# Solenoid_6.net
KiCad netlist of a schematic drawn in EAGLE
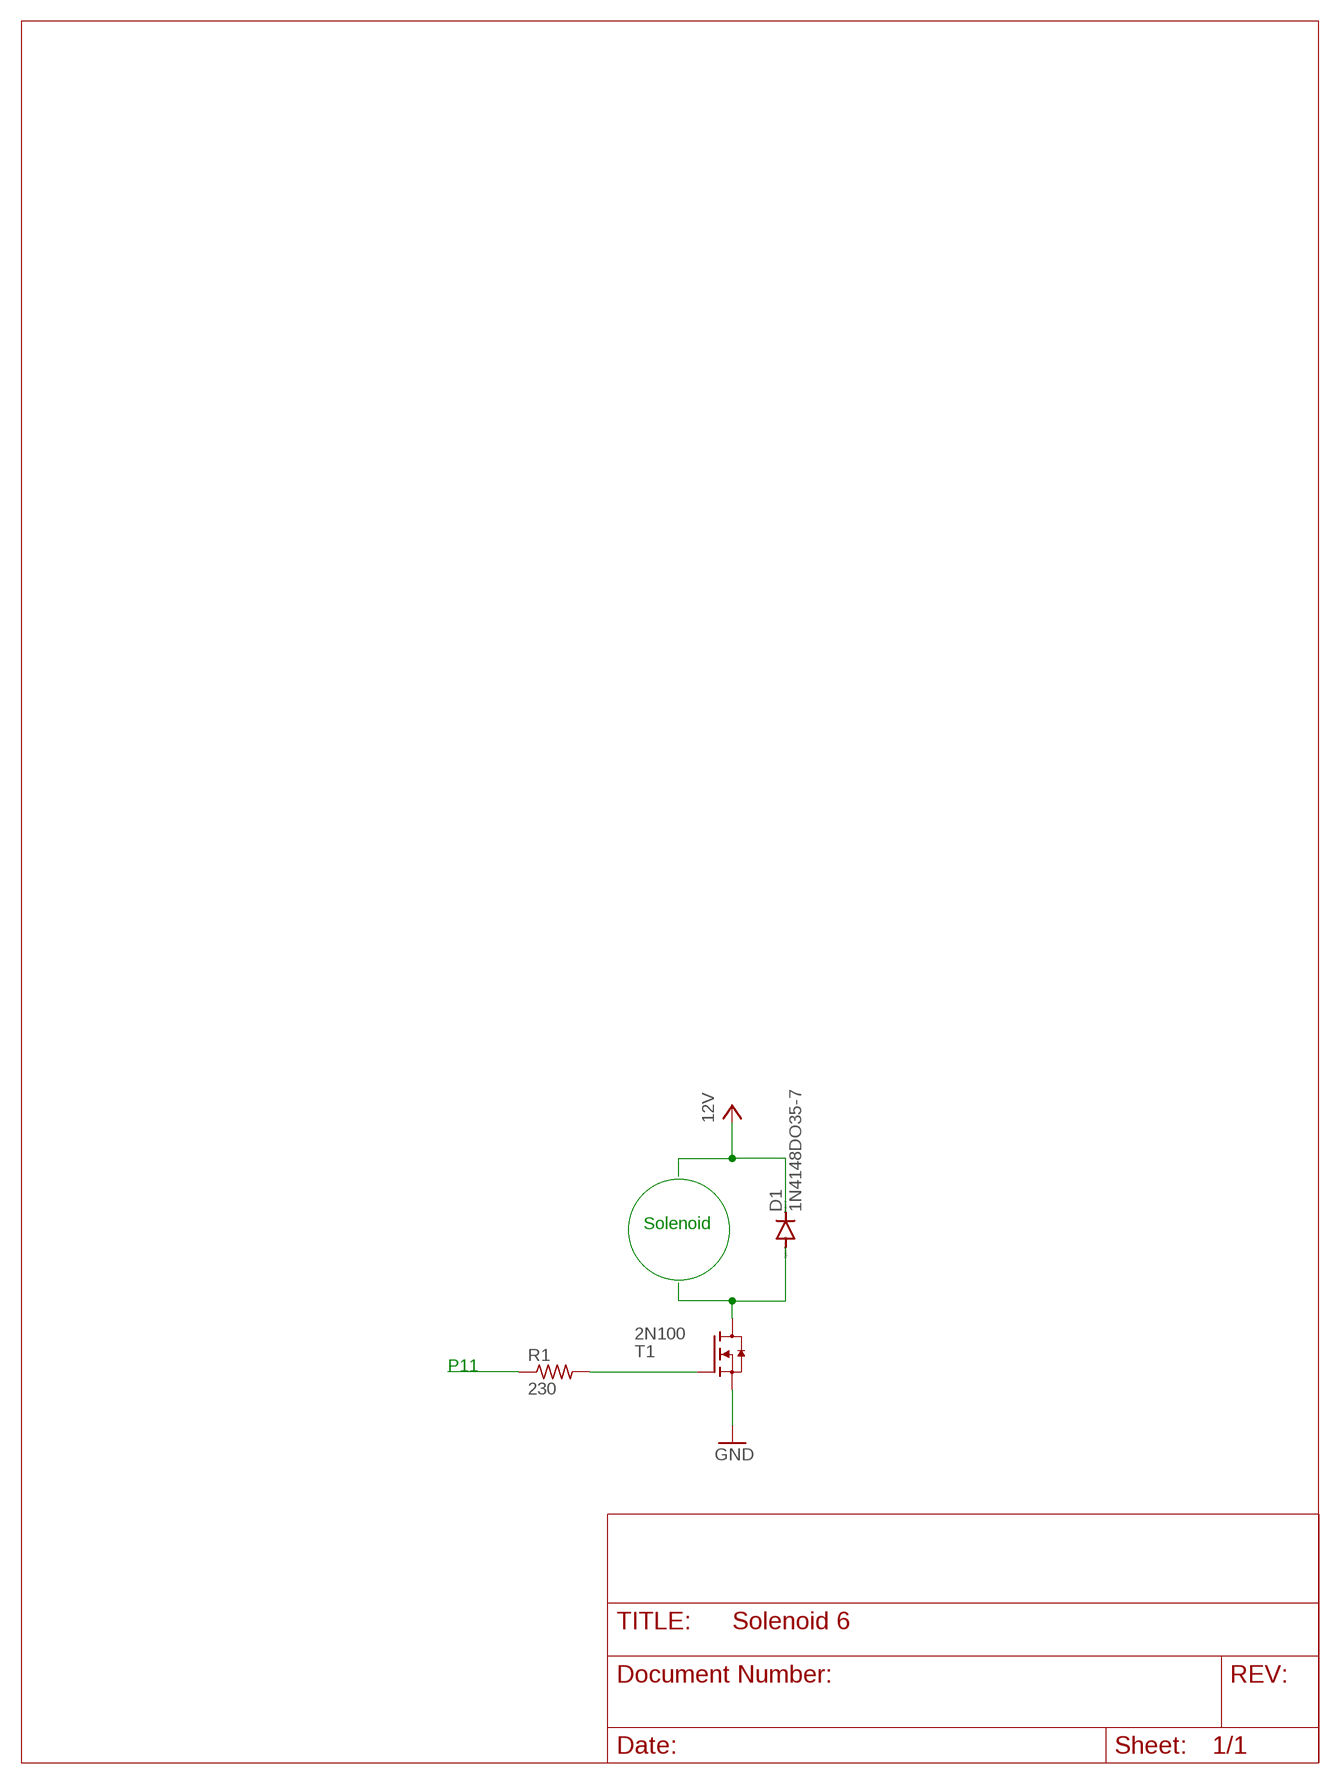
[diagram p0: schematic, sheet 1]

(export (version "E")
  (design (tool "Eeschema 10.0.6"))
  (components
    (comp (ref "D1")
      (value "1N4148DO35-7")
      (footprint "eagle-import:DO35-7")
      (libsource (lib "eagle-import") (part "1N4148DO35-7"))
    )
    (comp (ref "R1")
      (value "230")
      (footprint "eagle-import:0204_7")
      (libsource (lib "eagle-import") (part "R-US_0204/7"))
    )
    (comp (ref "T1")
      (value "2N100")
      (footprint "eagle-import:PG-TO263-7-3")
      (libsource (lib "eagle-import") (part "IPB180N06S4-H1"))
    )
  )
  (nets
    (net (code "1") (name "12V") (class "Default")
      (node (ref "D1") (pin "C") (pinfunction "C_C") (pintype "passive"))
    )
    (net (code "2") (name "GND") (class "Default")
      (node (ref "T1") (pin "2") (pinfunction "S_2") (pintype "passive"))
      (node (ref "T1") (pin "3") (pinfunction "S_3") (pintype "passive"))
      (node (ref "T1") (pin "5") (pinfunction "S_5") (pintype "passive"))
      (node (ref "T1") (pin "6") (pinfunction "S_6") (pintype "passive"))
      (node (ref "T1") (pin "7") (pinfunction "S_7") (pintype "passive"))
    )
    (net (code "3") (name "Net-(T1-D)") (class "Default")
      (node (ref "D1") (pin "A") (pinfunction "A_A") (pintype "passive"))
      (node (ref "T1") (pin "8") (pinfunction "D_8") (pintype "passive"))
    )
    (net (code "4") (name "Net-(T1-G)") (class "Default")
      (node (ref "R1") (pin "2") (pinfunction "2_2") (pintype "passive"))
      (node (ref "T1") (pin "1") (pinfunction "G_1") (pintype "passive"))
    )
    (net (code "5") (name "unconnected-(R1-Pad1)") (class "Default")
      (node (ref "R1") (pin "1") (pinfunction "1_1") (pintype "passive"))
    )
  )
)
